# protecao.net
KiCad netlist of a schematic drawn in Altium Designer
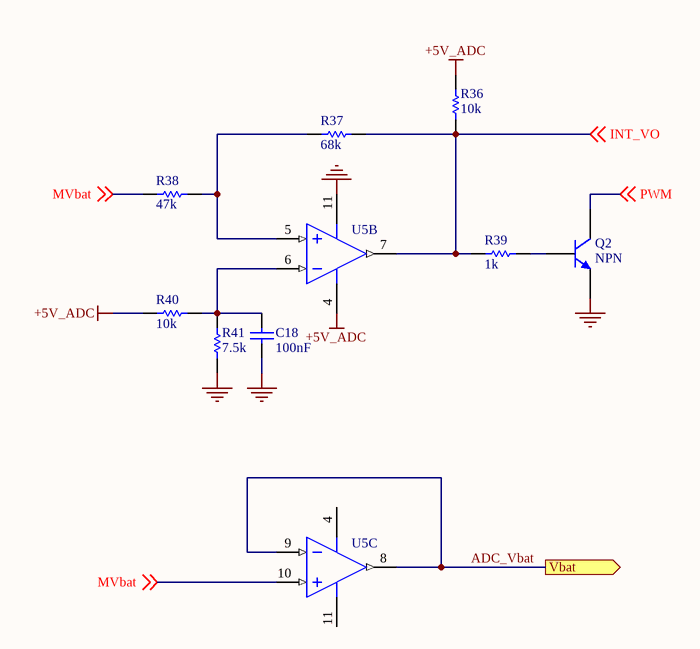
[diagram p0: protecao.SchDoc]

(export (version "E")
  (design (tool "Eeschema 10.0.6"))
  (components
    (comp (ref "C18")
      (value "100nF")
      (footprint "6-0805_M")
      (description "Capacitor")
      (fields (field (name "PUBLISHER") "Altium Limited"))
      (libsource (lib "ControladorCarga") (part "Cap_3"))
    )
    (comp (ref "Q2")
      (value "NPN")
      (footprint "TO-226-AA")
      (description "NPN Bipolar Transistor")
      (fields (field (name "PUBLISHER") "Altium Limited"))
      (libsource (lib "Miscellaneous Devices") (part "NPN"))
    )
    (comp (ref "R36")
      (value "10k")
      (footprint "6-0805_M")
      (description "Resistor")
      (fields (field (name "PUBLISHER") "Altium Limited"))
      (libsource (lib "ControladorCarga") (part "Res1"))
    )
    (comp (ref "R37")
      (value "68k")
      (footprint "6-0805_M")
      (description "Resistor")
      (fields (field (name "PUBLISHER") "Altium Limited"))
      (libsource (lib "ControladorCarga") (part "Res1"))
    )
    (comp (ref "R38")
      (value "47k")
      (footprint "6-0805_M")
      (description "Resistor")
      (fields (field (name "PUBLISHER") "Altium Limited"))
      (libsource (lib "ControladorCarga") (part "Res1"))
    )
    (comp (ref "R39")
      (value "1k")
      (footprint "6-0805_M")
      (description "Resistor")
      (fields (field (name "PUBLISHER") "Altium Limited"))
      (libsource (lib "ControladorCarga") (part "Res1"))
    )
    (comp (ref "R40")
      (value "10k")
      (footprint "6-0805_M")
      (description "Resistor")
      (fields (field (name "PUBLISHER") "Altium Limited"))
      (libsource (lib "ControladorCarga") (part "Res1"))
    )
    (comp (ref "R41")
      (value "7.5k")
      (footprint "6-0805_M")
      (description "Resistor")
      (fields (field (name "PUBLISHER") "Altium Limited"))
      (libsource (lib "ControladorCarga") (part "Res1"))
    )
    (comp (ref "U5")
      (value "LP324M")
      (footprint "M14A_M")
      (description "Micropower Quad Operational Amplifier")
      (fields
        (field (name "MANUFACTURER") "National Semiconductor")
        (field (name "DIGIKEYPARTNUMBER") "LP324MXCT-ND")
        (field (name "PUBLISHER") "Altium Limited")
      )
      (libsource (lib "ControladorCarga") (part "LP324M"))
    )
  )
  (nets
    (net (code "1") (name "+5V_ADC") (class "Default")
      (node (ref "R36") (pin "1") (pinfunction "1_1") (pintype "passive"))
      (node (ref "R40") (pin "1") (pinfunction "1_1") (pintype "passive"))
      (node (ref "U5") (pin "4") (pinfunction "V+_4") (pintype "power_in"))
    )
    (net (code "2") (name "/ADC_Vbat") (class "Default")
      (node (ref "U5") (pin "8") (pinfunction "OUT3_8") (pintype "output"))
      (node (ref "U5") (pin "9") (pinfunction "IN3-_9") (pintype "input"))
    )
    (net (code "3") (name "GND") (class "Default")
      (node (ref "C18") (pin "1") (pinfunction "1_1") (pintype "passive"))
      (node (ref "Q2") (pin "3") (pinfunction "E_3") (pintype "passive"))
      (node (ref "R41") (pin "1") (pinfunction "1_1") (pintype "passive"))
      (node (ref "U5") (pin "11") (pinfunction "GND_11") (pintype "power_in"))
    )
    (net (code "4") (name "INT_VO") (class "Default")
      (node (ref "R36") (pin "2") (pinfunction "2_2") (pintype "passive"))
      (node (ref "R37") (pin "2") (pinfunction "2_2") (pintype "passive"))
      (node (ref "R39") (pin "1") (pinfunction "1_1") (pintype "passive"))
      (node (ref "U5") (pin "7") (pinfunction "OUT2_7") (pintype "output"))
    )
    (net (code "5") (name "MVbat") (class "Default")
      (node (ref "R38") (pin "1") (pinfunction "1_1") (pintype "passive"))
      (node (ref "U5") (pin "10") (pinfunction "IN3+_10") (pintype "input"))
    )
    (net (code "6") (name "Net-(Q2-B)") (class "Default")
      (node (ref "Q2") (pin "2") (pinfunction "B_2") (pintype "passive"))
      (node (ref "R39") (pin "2") (pinfunction "2_2") (pintype "passive"))
    )
    (net (code "7") (name "Net-(U5B-IN2+)") (class "Default")
      (node (ref "R37") (pin "1") (pinfunction "1_1") (pintype "passive"))
      (node (ref "R38") (pin "2") (pinfunction "2_2") (pintype "passive"))
      (node (ref "U5") (pin "5") (pinfunction "IN2+_5") (pintype "input"))
    )
    (net (code "8") (name "Net-(U5B-IN2-)") (class "Default")
      (node (ref "C18") (pin "2") (pinfunction "2_2") (pintype "passive"))
      (node (ref "R40") (pin "2") (pinfunction "2_2") (pintype "passive"))
      (node (ref "R41") (pin "2") (pinfunction "2_2") (pintype "passive"))
      (node (ref "U5") (pin "6") (pinfunction "IN2-_6") (pintype "input"))
    )
    (net (code "9") (name "PWM") (class "Default")
      (node (ref "Q2") (pin "1") (pinfunction "C_1") (pintype "passive"))
    )
    (net (code "10") (name "unconnected-(U5C-GND-Pad11)") (class "Default")
      (node (ref "U5") (pin "11") (pinfunction "GND_11") (pintype "power_in"))
    )
    (net (code "11") (name "unconnected-(U5C-V+-Pad4)") (class "Default")
      (node (ref "U5") (pin "4") (pinfunction "V+_4") (pintype "power_in"))
    )
  )
)
